# bq24650_charger.net
KiCad netlist of a schematic drawn in EAGLE
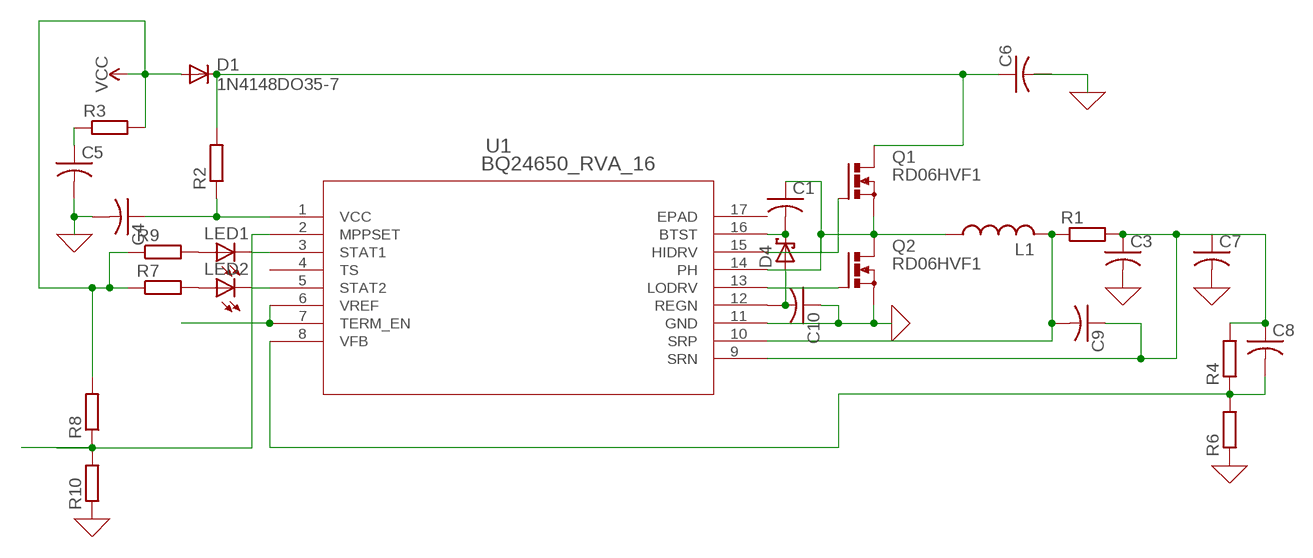
[diagram p0: schematic, sheet 1]

(export (version "E")
  (design (tool "Eeschema 10.0.6"))
  (components
    (comp (ref "C1")
      (value "C-USC2220K")
      (footprint "eagle-import:C2220K")
      (libsource (lib "eagle-import") (part "C-USC2220K"))
    )
    (comp (ref "C3")
      (value "C-USC2220K")
      (footprint "eagle-import:C2220K")
      (libsource (lib "eagle-import") (part "C-USC2220K"))
    )
    (comp (ref "C4")
      (value "C-USC2220K")
      (footprint "eagle-import:C2220K")
      (libsource (lib "eagle-import") (part "C-USC2220K"))
    )
    (comp (ref "C5")
      (value "C-USC2220K")
      (footprint "eagle-import:C2220K")
      (libsource (lib "eagle-import") (part "C-USC2220K"))
    )
    (comp (ref "C6")
      (value "C-USC2220K")
      (footprint "eagle-import:C2220K")
      (libsource (lib "eagle-import") (part "C-USC2220K"))
    )
    (comp (ref "C7")
      (value "C-USC2220K")
      (footprint "eagle-import:C2220K")
      (libsource (lib "eagle-import") (part "C-USC2220K"))
    )
    (comp (ref "C8")
      (value "C-USC2220K")
      (footprint "eagle-import:C2220K")
      (libsource (lib "eagle-import") (part "C-USC2220K"))
    )
    (comp (ref "C9")
      (value "C-USC2220K")
      (footprint "eagle-import:C2220K")
      (libsource (lib "eagle-import") (part "C-USC2220K"))
    )
    (comp (ref "C10")
      (value "C-USC2220K")
      (footprint "eagle-import:C2220K")
      (libsource (lib "eagle-import") (part "C-USC2220K"))
    )
    (comp (ref "D1")
      (value "1N4148DO35-7")
      (footprint "eagle-import:DO35-7")
      (libsource (lib "eagle-import") (part "1N4148DO35-7"))
    )
    (comp (ref "D4")
      (value "SCHOTTKY-DIODECB429-15")
      (footprint "eagle-import:CB429-15")
      (libsource (lib "eagle-import") (part "SCHOTTKY-DIODECB429-15"))
    )
    (comp (ref "L1")
      (value "L-US0204/5")
      (footprint "eagle-import:0204_5")
      (libsource (lib "eagle-import") (part "L-US0204/5"))
    )
    (comp (ref "LED1")
      (value "LED")
      (footprint "eagle-import:SMARTLED-TTW")
      (libsource (lib "eagle-import") (part "LED"))
    )
    (comp (ref "LED2")
      (value "LED")
      (footprint "eagle-import:SMARTLED-TTW")
      (libsource (lib "eagle-import") (part "LED"))
    )
    (comp (ref "Q1")
      (value "RD06HVF1")
      (footprint "eagle-import:RD06HVF1")
      (libsource (lib "eagle-import") (part "RD06HVF1"))
    )
    (comp (ref "Q2")
      (value "RD06HVF1")
      (footprint "eagle-import:RD06HVF1")
      (libsource (lib "eagle-import") (part "RD06HVF1"))
    )
    (comp (ref "R1") (value "R") (footprint "eagle-import:R0805") (libsource (lib "eagle-import") (part "R")))
    (comp (ref "R2") (value "R") (footprint "eagle-import:R0805") (libsource (lib "eagle-import") (part "R")))
    (comp (ref "R3") (value "R") (footprint "eagle-import:R0805") (libsource (lib "eagle-import") (part "R")))
    (comp (ref "R4") (value "R") (footprint "eagle-import:R0805") (libsource (lib "eagle-import") (part "R")))
    (comp (ref "R6") (value "R") (footprint "eagle-import:R0805") (libsource (lib "eagle-import") (part "R")))
    (comp (ref "R7") (value "R") (footprint "eagle-import:R0805") (libsource (lib "eagle-import") (part "R")))
    (comp (ref "R8") (value "R") (footprint "eagle-import:R0805") (libsource (lib "eagle-import") (part "R")))
    (comp (ref "R9") (value "R") (footprint "eagle-import:R0805") (libsource (lib "eagle-import") (part "R")))
    (comp (ref "R10")
      (value "R")
      (footprint "eagle-import:R0805")
      (libsource (lib "eagle-import") (part "R"))
    )
    (comp (ref "U1")
      (value "BQ24650_RVA_16")
      (footprint "eagle-import:RVA16_2P14X2P14")
      (fields
        (field (name "GENERIC_PART_NUMBER") "BQ24650")
        (field (name "MANUFACTURER") "Texas Instruments")
      )
      (libsource (lib "eagle-import") (part "BQ24650_RVA_16"))
    )
  )
  (nets
    (net (code "1") (name "/EPAD") (class "Default")
      (node (ref "U1") (pin "17") (pinfunction "EPAD_17") (pintype "power_in"))
    )
    (net (code "2") (name "GND") (class "Default")
      (node (ref "C10") (pin "1") (pinfunction "1_1") (pintype "passive"))
      (node (ref "C3") (pin "2") (pinfunction "2_2") (pintype "passive"))
      (node (ref "C4") (pin "2") (pinfunction "2_2") (pintype "passive"))
      (node (ref "C5") (pin "2") (pinfunction "2_2") (pintype "passive"))
      (node (ref "C7") (pin "2") (pinfunction "2_2") (pintype "passive"))
      (node (ref "Q2") (pin "2") (pinfunction "S_2") (pintype "passive"))
      (node (ref "R10") (pin "1") (pinfunction "1_1") (pintype "passive"))
      (node (ref "R6") (pin "1") (pinfunction "1_1") (pintype "passive"))
      (node (ref "U1") (pin "11") (pinfunction "GND_11") (pintype "power_in"))
    )
    (net (code "3") (name "Net-(C5-Pad1)") (class "Default")
      (node (ref "C5") (pin "1") (pinfunction "1_1") (pintype "passive"))
      (node (ref "R3") (pin "1") (pinfunction "1_1") (pintype "passive"))
    )
    (net (code "4") (name "Net-(LED1-A)") (class "Default")
      (node (ref "LED1") (pin "A@1") (pinfunction "A_A@1") (pintype "passive"))
      (node (ref "R9") (pin "2") (pinfunction "2_2") (pintype "passive"))
    )
    (net (code "5") (name "Net-(LED1-C)") (class "Default")
      (node (ref "LED1") (pin "C@1") (pinfunction "C_C@1") (pintype "passive"))
      (node (ref "U1") (pin "3") (pinfunction "STAT1_3") (pintype "output"))
    )
    (net (code "6") (name "Net-(LED2-A)") (class "Default")
      (node (ref "LED2") (pin "A@1") (pinfunction "A_A@1") (pintype "passive"))
      (node (ref "R7") (pin "2") (pinfunction "2_2") (pintype "passive"))
    )
    (net (code "7") (name "Net-(LED2-C)") (class "Default")
      (node (ref "LED2") (pin "C@1") (pinfunction "C_C@1") (pintype "passive"))
      (node (ref "U1") (pin "5") (pinfunction "STAT2_5") (pintype "output"))
    )
    (net (code "8") (name "Net-(Q1-D)") (class "Default")
      (node (ref "C6") (pin "1") (pinfunction "1_1") (pintype "passive"))
      (node (ref "D1") (pin "C") (pinfunction "C_C") (pintype "passive"))
      (node (ref "Q1") (pin "3") (pinfunction "D_3") (pintype "passive"))
      (node (ref "R2") (pin "2") (pinfunction "2_2") (pintype "passive"))
    )
    (net (code "9") (name "Net-(Q1-G)") (class "Default")
      (node (ref "C1") (pin "1") (pinfunction "1_1") (pintype "passive"))
      (node (ref "L1") (pin "1") (pinfunction "1_1") (pintype "passive"))
      (node (ref "Q1") (pin "1") (pinfunction "G_1") (pintype "passive"))
      (node (ref "Q1") (pin "2") (pinfunction "S_2") (pintype "passive"))
      (node (ref "Q2") (pin "3") (pinfunction "D_3") (pintype "passive"))
      (node (ref "U1") (pin "14") (pinfunction "PH_14") (pintype "power_in"))
      (node (ref "U1") (pin "15") (pinfunction "HIDRV_15") (pintype "output"))
    )
    (net (code "10") (name "Net-(Q2-G)") (class "Default")
      (node (ref "Q2") (pin "1") (pinfunction "G_1") (pintype "passive"))
      (node (ref "U1") (pin "13") (pinfunction "LODRV_13") (pintype "output"))
    )
    (net (code "11") (name "Net-(U1-BTST)") (class "Default")
      (node (ref "C1") (pin "2") (pinfunction "2_2") (pintype "passive"))
      (node (ref "D4") (pin "C") (pinfunction "C_C") (pintype "passive"))
      (node (ref "U1") (pin "16") (pinfunction "BTST_16") (pintype "power_in"))
    )
    (net (code "12") (name "Net-(U1-MPPSET)") (class "Default")
      (node (ref "R10") (pin "2") (pinfunction "2_2") (pintype "passive"))
      (node (ref "R8") (pin "1") (pinfunction "1_1") (pintype "passive"))
      (node (ref "U1") (pin "2") (pinfunction "MPPSET_2") (pintype "input"))
    )
    (net (code "13") (name "Net-(U1-REGN)") (class "Default")
      (node (ref "C10") (pin "2") (pinfunction "2_2") (pintype "passive"))
      (node (ref "U1") (pin "12") (pinfunction "REGN_12") (pintype "power_in"))
    )
    (net (code "14") (name "Net-(U1-SRN)") (class "Default")
      (node (ref "C3") (pin "1") (pinfunction "1_1") (pintype "passive"))
      (node (ref "C7") (pin "1") (pinfunction "1_1") (pintype "passive"))
      (node (ref "C8") (pin "1") (pinfunction "1_1") (pintype "passive"))
      (node (ref "C9") (pin "1") (pinfunction "1_1") (pintype "passive"))
      (node (ref "R1") (pin "2") (pinfunction "2_2") (pintype "passive"))
      (node (ref "R4") (pin "2") (pinfunction "2_2") (pintype "passive"))
      (node (ref "U1") (pin "9") (pinfunction "SRN_9") (pintype "input"))
    )
    (net (code "15") (name "Net-(U1-SRP)") (class "Default")
      (node (ref "C9") (pin "2") (pinfunction "2_2") (pintype "passive"))
      (node (ref "L1") (pin "2") (pinfunction "2_2") (pintype "passive"))
      (node (ref "R1") (pin "1") (pinfunction "1_1") (pintype "passive"))
      (node (ref "U1") (pin "10") (pinfunction "SRP_10") (pintype "bidirectional"))
    )
    (net (code "16") (name "Net-(U1-TERM_EN)") (class "Default")
      (node (ref "U1") (pin "6") (pinfunction "VREF_6") (pintype "power_in"))
      (node (ref "U1") (pin "7") (pinfunction "TERM_EN_7") (pintype "input"))
    )
    (net (code "17") (name "Net-(U1-VCC)") (class "Default")
      (node (ref "C4") (pin "1") (pinfunction "1_1") (pintype "passive"))
      (node (ref "R2") (pin "1") (pinfunction "1_1") (pintype "passive"))
      (node (ref "U1") (pin "1") (pinfunction "VCC_1") (pintype "power_in"))
    )
    (net (code "18") (name "Net-(U1-VFB)") (class "Default")
      (node (ref "C8") (pin "2") (pinfunction "2_2") (pintype "passive"))
      (node (ref "R4") (pin "1") (pinfunction "1_1") (pintype "passive"))
      (node (ref "R6") (pin "2") (pinfunction "2_2") (pintype "passive"))
      (node (ref "U1") (pin "8") (pinfunction "VFB_8") (pintype "input"))
    )
    (net (code "19") (name "VCC") (class "Default")
      (node (ref "D1") (pin "A") (pinfunction "A_A") (pintype "passive"))
      (node (ref "R3") (pin "2") (pinfunction "2_2") (pintype "passive"))
      (node (ref "R7") (pin "1") (pinfunction "1_1") (pintype "passive"))
      (node (ref "R8") (pin "2") (pinfunction "2_2") (pintype "passive"))
      (node (ref "R9") (pin "1") (pinfunction "1_1") (pintype "passive"))
    )
    (net (code "20") (name "unconnected-(C6-Pad2)") (class "Default")
      (node (ref "C6") (pin "2") (pinfunction "2_2") (pintype "passive"))
    )
    (net (code "21") (name "unconnected-(D4-PadA)") (class "Default")
      (node (ref "D4") (pin "A") (pinfunction "A_A") (pintype "passive"))
    )
    (net (code "22") (name "unconnected-(U1-TS-Pad4)") (class "Default")
      (node (ref "U1") (pin "4") (pinfunction "TS_4") (pintype "input"))
    )
  )
)
